# FA18_AMPCD.net
KiCad netlist of a schematic drawn in Altium Designer
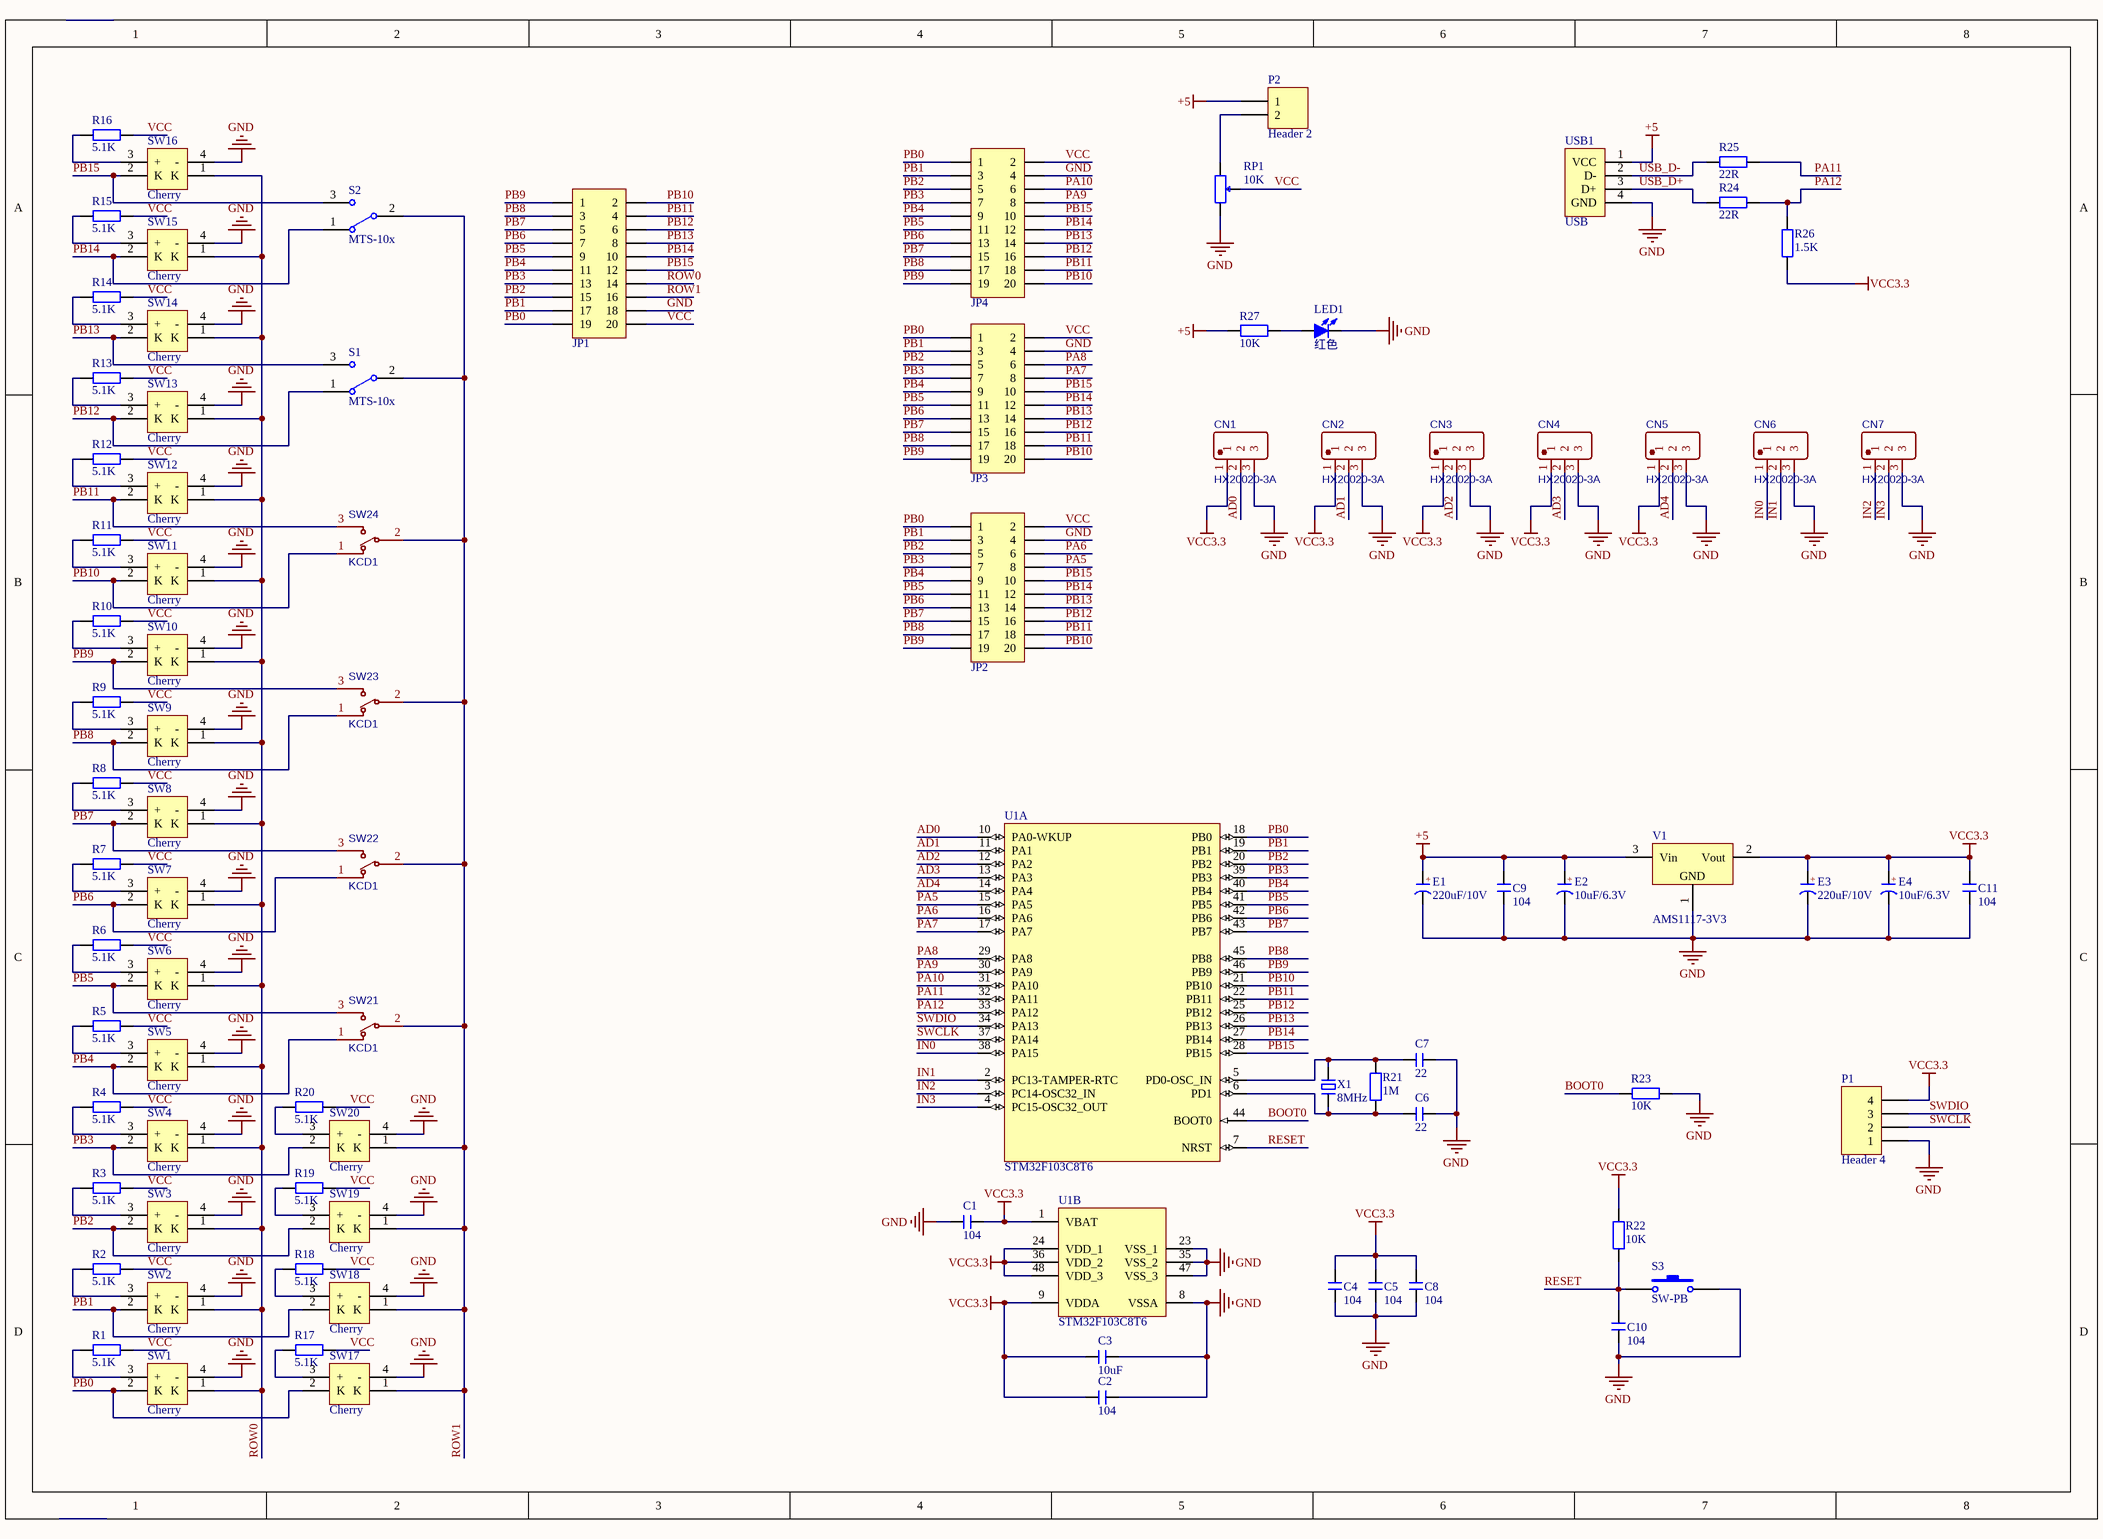
[diagram p0: FA18_AMPCD.SchDoc]

(export (version "E")
  (design (tool "Eeschema 10.0.6"))
  (components
    (comp (ref "C1")
      (value "104")
      (footprint "C 0603_L")
      (description "贴片电容")
      (libsource (lib "wyc_lib") (part "C"))
    )
    (comp (ref "C2")
      (value "104")
      (footprint "C 0603_L")
      (description "贴片电容")
      (libsource (lib "wyc_lib") (part "C"))
    )
    (comp (ref "C3")
      (value "10uF")
      (footprint "C 0603_L")
      (description "贴片电容")
      (libsource (lib "wyc_lib") (part "C"))
    )
    (comp (ref "C4")
      (value "104")
      (footprint "C 0603_L")
      (description "贴片电容")
      (libsource (lib "wyc_lib") (part "C"))
    )
    (comp (ref "C5")
      (value "104")
      (footprint "C 0603_L")
      (description "贴片电容")
      (libsource (lib "wyc_lib") (part "C"))
    )
    (comp (ref "C6")
      (value "22")
      (footprint "C 0603_L")
      (description "贴片电容")
      (libsource (lib "wyc_lib") (part "C"))
    )
    (comp (ref "C7")
      (value "22")
      (footprint "C 0603_L")
      (description "贴片电容")
      (libsource (lib "wyc_lib") (part "C"))
    )
    (comp (ref "C8")
      (value "104")
      (footprint "C 0603_L")
      (description "贴片电容")
      (libsource (lib "wyc_lib") (part "C"))
    )
    (comp (ref "C9")
      (value "104")
      (footprint "C 0603_L")
      (description "贴片电容")
      (libsource (lib "wyc_lib") (part "C"))
    )
    (comp (ref "C10")
      (value "104")
      (footprint "C 0603_L")
      (description "贴片电容")
      (libsource (lib "wyc_lib") (part "C"))
    )
    (comp (ref "C11")
      (value "104")
      (footprint "C 0603_L")
      (description "贴片电容")
      (libsource (lib "wyc_lib") (part "C"))
    )
    (comp (ref "CN1")
      (value "HX20020-3A")
      (footprint "CONN-TH_3P-P2.00_HX20020-3A")
      (fields (field (name "BOM_SUPPLIER PART") "C442245") (field (name "CONTRIBUTOR") "LCSC"))
      (libsource (lib "lichuang_lib") (part "HX20020-3A"))
    )
    (comp (ref "CN2")
      (value "HX20020-3A")
      (footprint "CONN-TH_3P-P2.00_HX20020-3A")
      (fields (field (name "BOM_SUPPLIER PART") "C442245") (field (name "CONTRIBUTOR") "LCSC"))
      (libsource (lib "lichuang_lib") (part "HX20020-3A"))
    )
    (comp (ref "CN3")
      (value "HX20020-3A")
      (footprint "CONN-TH_3P-P2.00_HX20020-3A")
      (fields (field (name "BOM_SUPPLIER PART") "C442245") (field (name "CONTRIBUTOR") "LCSC"))
      (libsource (lib "lichuang_lib") (part "HX20020-3A"))
    )
    (comp (ref "CN4")
      (value "HX20020-3A")
      (footprint "CONN-TH_3P-P2.00_HX20020-3A")
      (fields (field (name "BOM_SUPPLIER PART") "C442245") (field (name "CONTRIBUTOR") "LCSC"))
      (libsource (lib "lichuang_lib") (part "HX20020-3A"))
    )
    (comp (ref "CN5")
      (value "HX20020-3A")
      (footprint "CONN-TH_3P-P2.00_HX20020-3A")
      (fields (field (name "BOM_SUPPLIER PART") "C442245") (field (name "CONTRIBUTOR") "LCSC"))
      (libsource (lib "lichuang_lib") (part "HX20020-3A"))
    )
    (comp (ref "CN6")
      (value "HX20020-3A")
      (footprint "CONN-TH_3P-P2.00_HX20020-3A")
      (fields (field (name "BOM_SUPPLIER PART") "C442245") (field (name "CONTRIBUTOR") "LCSC"))
      (libsource (lib "lichuang_lib") (part "HX20020-3A"))
    )
    (comp (ref "CN7")
      (value "HX20020-3A")
      (footprint "CONN-TH_3P-P2.00_HX20020-3A")
      (fields (field (name "BOM_SUPPLIER PART") "C442245") (field (name "CONTRIBUTOR") "LCSC"))
      (libsource (lib "lichuang_lib") (part "HX20020-3A"))
    )
    (comp (ref "E1")
      (value "220uF/10V")
      (footprint "CM D(6.3*5.4)")
      (description "贴片电解电容")
      (fields (field (name "版权归属") "封装库来自淘宝 ID：黄晶宝石"))
      (libsource (lib "wyc_lib") (part "CE_SMD"))
    )
    (comp (ref "E2")
      (value "10uF/6.3V")
      (footprint "CD B(3528)")
      (description "贴片钽电容")
      (libsource (lib "wyc_lib") (part "CT"))
    )
    (comp (ref "E3")
      (value "220uF/10V")
      (footprint "CM D(6.3*5.4)")
      (description "贴片电解电容")
      (fields (field (name "版权归属") "封装库来自淘宝 ID：黄晶宝石"))
      (libsource (lib "wyc_lib") (part "CE_SMD"))
    )
    (comp (ref "E4")
      (value "10uF/6.3V")
      (footprint "CD B(3528)")
      (description "贴片钽电容")
      (libsource (lib "wyc_lib") (part "CT"))
    )
    (comp (ref "JP1")
      (value "Header 2X10")
      (footprint "PHB2.0-LI-2x10P")
      (description "10*2P接插件")
      (libsource (lib "wyc_lib") (part "Header 10X2"))
    )
    (comp (ref "JP2")
      (value "Header 2X10")
      (footprint "PHB2.0-LI-2x10P")
      (description "10*2P接插件")
      (libsource (lib "wyc_lib") (part "Header 10X2"))
    )
    (comp (ref "JP3")
      (value "Header 2X10")
      (footprint "PHB2.0-LI-2x10P")
      (description "10*2P接插件")
      (libsource (lib "wyc_lib") (part "Header 10X2"))
    )
    (comp (ref "JP4")
      (value "Header 2X10")
      (footprint "PHB2.0-LI-2x10P")
      (description "10*2P接插件")
      (libsource (lib "wyc_lib") (part "Header 10X2"))
    )
    (comp (ref "LED1")
      (value "红色")
      (footprint "LED 0603W")
      (description "贴片LED")
      (fields (field (name "版权归属") "封装库来自淘宝 ID：黄晶宝石"))
      (libsource (lib "wyc_lib") (part "LED-SMD"))
    )
    (comp (ref "P1")
      (value "Header 4")
      (footprint "HDR1X4")
      (description "Header, 4-Pin")
      (fields (field (name "PUBLISHER") "Altium Limited"))
      (libsource (lib "Miscellaneous Connectors") (part "Header 4"))
    )
    (comp (ref "P2")
      (value "Header 2")
      (footprint "HDR1X2")
      (description "Header, 2-Pin")
      (fields (field (name "PUBLISHER") "Altium Limited"))
      (libsource (lib "Miscellaneous Connectors") (part "Header 2"))
    )
    (comp (ref "R1")
      (value "5.1K")
      (footprint "R 0603_L")
      (description "贴片电阻")
      (fields (field (name "版权归属") "来自淘宝 ID：黄晶宝石"))
      (libsource (lib "wyc_lib") (part "R"))
    )
    (comp (ref "R2")
      (value "5.1K")
      (footprint "R 0603_L")
      (description "贴片电阻")
      (fields (field (name "版权归属") "来自淘宝 ID：黄晶宝石"))
      (libsource (lib "wyc_lib") (part "R"))
    )
    (comp (ref "R3")
      (value "5.1K")
      (footprint "R 0603_L")
      (description "贴片电阻")
      (fields (field (name "版权归属") "来自淘宝 ID：黄晶宝石"))
      (libsource (lib "wyc_lib") (part "R"))
    )
    (comp (ref "R4")
      (value "5.1K")
      (footprint "R 0603_L")
      (description "贴片电阻")
      (fields (field (name "版权归属") "来自淘宝 ID：黄晶宝石"))
      (libsource (lib "wyc_lib") (part "R"))
    )
    (comp (ref "R5")
      (value "5.1K")
      (footprint "R 0603_L")
      (description "贴片电阻")
      (fields (field (name "版权归属") "来自淘宝 ID：黄晶宝石"))
      (libsource (lib "wyc_lib") (part "R"))
    )
    (comp (ref "R6")
      (value "5.1K")
      (footprint "R 0603_L")
      (description "贴片电阻")
      (fields (field (name "版权归属") "来自淘宝 ID：黄晶宝石"))
      (libsource (lib "wyc_lib") (part "R"))
    )
    (comp (ref "R7")
      (value "5.1K")
      (footprint "R 0603_L")
      (description "贴片电阻")
      (fields (field (name "版权归属") "来自淘宝 ID：黄晶宝石"))
      (libsource (lib "wyc_lib") (part "R"))
    )
    (comp (ref "R8")
      (value "5.1K")
      (footprint "R 0603_L")
      (description "贴片电阻")
      (fields (field (name "版权归属") "来自淘宝 ID：黄晶宝石"))
      (libsource (lib "wyc_lib") (part "R"))
    )
    (comp (ref "R9")
      (value "5.1K")
      (footprint "R 0603_L")
      (description "贴片电阻")
      (fields (field (name "版权归属") "来自淘宝 ID：黄晶宝石"))
      (libsource (lib "wyc_lib") (part "R"))
    )
    (comp (ref "R10")
      (value "5.1K")
      (footprint "R 0603_L")
      (description "贴片电阻")
      (fields (field (name "版权归属") "来自淘宝 ID：黄晶宝石"))
      (libsource (lib "wyc_lib") (part "R"))
    )
    (comp (ref "R11")
      (value "5.1K")
      (footprint "R 0603_L")
      (description "贴片电阻")
      (fields (field (name "版权归属") "来自淘宝 ID：黄晶宝石"))
      (libsource (lib "wyc_lib") (part "R"))
    )
    (comp (ref "R12")
      (value "5.1K")
      (footprint "R 0603_L")
      (description "贴片电阻")
      (fields (field (name "版权归属") "来自淘宝 ID：黄晶宝石"))
      (libsource (lib "wyc_lib") (part "R"))
    )
    (comp (ref "R13")
      (value "5.1K")
      (footprint "R 0603_L")
      (description "贴片电阻")
      (fields (field (name "版权归属") "来自淘宝 ID：黄晶宝石"))
      (libsource (lib "wyc_lib") (part "R"))
    )
    (comp (ref "R14")
      (value "5.1K")
      (footprint "R 0603_L")
      (description "贴片电阻")
      (fields (field (name "版权归属") "来自淘宝 ID：黄晶宝石"))
      (libsource (lib "wyc_lib") (part "R"))
    )
    (comp (ref "R15")
      (value "5.1K")
      (footprint "R 0603_L")
      (description "贴片电阻")
      (fields (field (name "版权归属") "来自淘宝 ID：黄晶宝石"))
      (libsource (lib "wyc_lib") (part "R"))
    )
    (comp (ref "R16")
      (value "5.1K")
      (footprint "R 0603_L")
      (description "贴片电阻")
      (fields (field (name "版权归属") "来自淘宝 ID：黄晶宝石"))
      (libsource (lib "wyc_lib") (part "R"))
    )
    (comp (ref "R17")
      (value "5.1K")
      (footprint "R 0603_L")
      (description "贴片电阻")
      (fields (field (name "版权归属") "来自淘宝 ID：黄晶宝石"))
      (libsource (lib "wyc_lib") (part "R"))
    )
    (comp (ref "R18")
      (value "5.1K")
      (footprint "R 0603_L")
      (description "贴片电阻")
      (fields (field (name "版权归属") "来自淘宝 ID：黄晶宝石"))
      (libsource (lib "wyc_lib") (part "R"))
    )
    (comp (ref "R19")
      (value "5.1K")
      (footprint "R 0603_L")
      (description "贴片电阻")
      (fields (field (name "版权归属") "来自淘宝 ID：黄晶宝石"))
      (libsource (lib "wyc_lib") (part "R"))
    )
    (comp (ref "R20")
      (value "5.1K")
      (footprint "R 0603_L")
      (description "贴片电阻")
      (fields (field (name "版权归属") "来自淘宝 ID：黄晶宝石"))
      (libsource (lib "wyc_lib") (part "R"))
    )
    (comp (ref "R21")
      (value "1M")
      (footprint "R 0603_L")
      (description "贴片电阻")
      (fields (field (name "版权归属") "来自淘宝 ID：黄晶宝石"))
      (libsource (lib "wyc_lib") (part "R"))
    )
    (comp (ref "R22")
      (value "10K")
      (footprint "R 0603_L")
      (description "贴片电阻")
      (fields (field (name "版权归属") "来自淘宝 ID：黄晶宝石"))
      (libsource (lib "wyc_lib") (part "R"))
    )
    (comp (ref "R23")
      (value "10K")
      (footprint "R 0603_L")
      (description "贴片电阻")
      (fields (field (name "版权归属") "来自淘宝 ID：黄晶宝石"))
      (libsource (lib "wyc_lib") (part "R"))
    )
    (comp (ref "R24")
      (value "22R")
      (footprint "R 0603_L")
      (description "贴片电阻")
      (fields (field (name "版权归属") "来自淘宝 ID：黄晶宝石"))
      (libsource (lib "wyc_lib") (part "R"))
    )
    (comp (ref "R25")
      (value "22R")
      (footprint "R 0603_L")
      (description "贴片电阻")
      (fields (field (name "版权归属") "来自淘宝 ID：黄晶宝石"))
      (libsource (lib "wyc_lib") (part "R"))
    )
    (comp (ref "R26")
      (value "1.5K")
      (footprint "R 0603_L")
      (description "贴片电阻")
      (fields (field (name "版权归属") "来自淘宝 ID：黄晶宝石"))
      (libsource (lib "wyc_lib") (part "R"))
    )
    (comp (ref "R27")
      (value "10K")
      (footprint "R 0603_L")
      (description "贴片电阻")
      (fields (field (name "版权归属") "来自淘宝 ID：黄晶宝石"))
      (libsource (lib "wyc_lib") (part "R"))
    )
    (comp (ref "RP1")
      (value "10K")
      (footprint "WH148-1-G15")
      (description "单联电位器")
      (fields (field (name "版权归属") "封装库来自淘宝 ID：黄晶宝石"))
      (libsource (lib "wyc_lib") (part "RP"))
    )
    (comp (ref "S1")
      (value "MTS-10x")
      (footprint "MTS-10x")
      (description "MTS10x系列3脚扭子开关")
      (fields (field (name "版权归属") "封装库来自淘宝 ID：黄晶宝石"))
      (libsource (lib "wyc_lib") (part "MTS-10x"))
    )
    (comp (ref "S2")
      (value "MTS-10x")
      (footprint "MTS-10x")
      (description "MTS10x系列3脚扭子开关")
      (fields (field (name "版权归属") "封装库来自淘宝 ID：黄晶宝石"))
      (libsource (lib "wyc_lib") (part "MTS-10x"))
    )
    (comp (ref "S3")
      (value "SW-PB")
      (footprint "SW_PB2_A1")
      (description "微动开关")
      (fields (field (name "PUBLISHER") "Altium Limited"))
      (libsource (lib "wyc_lib") (part "SW-PB"))
    )
    (comp (ref "SW1")
      (value "Cherry")
      (footprint "LSW DIP-CHERRY")
      (description "带灯机械按键开关")
      (fields (field (name "版权归属") "封装库来自淘宝 ID：黄晶宝石"))
      (libsource (lib "wyc_lib") (part "LSW"))
    )
    (comp (ref "SW2")
      (value "Cherry")
      (footprint "LSW DIP-CHERRY")
      (description "带灯机械按键开关")
      (fields (field (name "版权归属") "封装库来自淘宝 ID：黄晶宝石"))
      (libsource (lib "wyc_lib") (part "LSW"))
    )
    (comp (ref "SW3")
      (value "Cherry")
      (footprint "LSW DIP-CHERRY")
      (description "带灯机械按键开关")
      (fields (field (name "版权归属") "封装库来自淘宝 ID：黄晶宝石"))
      (libsource (lib "wyc_lib") (part "LSW"))
    )
    (comp (ref "SW4")
      (value "Cherry")
      (footprint "LSW DIP-CHERRY")
      (description "带灯机械按键开关")
      (fields (field (name "版权归属") "封装库来自淘宝 ID：黄晶宝石"))
      (libsource (lib "wyc_lib") (part "LSW"))
    )
    (comp (ref "SW5")
      (value "Cherry")
      (footprint "LSW DIP-CHERRY")
      (description "带灯机械按键开关")
      (fields (field (name "版权归属") "封装库来自淘宝 ID：黄晶宝石"))
      (libsource (lib "wyc_lib") (part "LSW"))
    )
    (comp (ref "SW6")
      (value "Cherry")
      (footprint "LSW DIP-CHERRY")
      (description "带灯机械按键开关")
      (fields (field (name "版权归属") "封装库来自淘宝 ID：黄晶宝石"))
      (libsource (lib "wyc_lib") (part "LSW"))
    )
    (comp (ref "SW7")
      (value "Cherry")
      (footprint "LSW DIP-CHERRY")
      (description "带灯机械按键开关")
      (fields (field (name "版权归属") "封装库来自淘宝 ID：黄晶宝石"))
      (libsource (lib "wyc_lib") (part "LSW"))
    )
    (comp (ref "SW8")
      (value "Cherry")
      (footprint "LSW DIP-CHERRY")
      (description "带灯机械按键开关")
      (fields (field (name "版权归属") "封装库来自淘宝 ID：黄晶宝石"))
      (libsource (lib "wyc_lib") (part "LSW"))
    )
    (comp (ref "SW9")
      (value "Cherry")
      (footprint "LSW DIP-CHERRY")
      (description "带灯机械按键开关")
      (fields (field (name "版权归属") "封装库来自淘宝 ID：黄晶宝石"))
      (libsource (lib "wyc_lib") (part "LSW"))
    )
    (comp (ref "SW10")
      (value "Cherry")
      (footprint "LSW DIP-CHERRY")
      (description "带灯机械按键开关")
      (fields (field (name "版权归属") "封装库来自淘宝 ID：黄晶宝石"))
      (libsource (lib "wyc_lib") (part "LSW"))
    )
    (comp (ref "SW11")
      (value "Cherry")
      (footprint "LSW DIP-CHERRY")
      (description "带灯机械按键开关")
      (fields (field (name "版权归属") "封装库来自淘宝 ID：黄晶宝石"))
      (libsource (lib "wyc_lib") (part "LSW"))
    )
    (comp (ref "SW12")
      (value "Cherry")
      (footprint "LSW DIP-CHERRY")
      (description "带灯机械按键开关")
      (fields (field (name "版权归属") "封装库来自淘宝 ID：黄晶宝石"))
      (libsource (lib "wyc_lib") (part "LSW"))
    )
    (comp (ref "SW13")
      (value "Cherry")
      (footprint "LSW DIP-CHERRY")
      (description "带灯机械按键开关")
      (fields (field (name "版权归属") "封装库来自淘宝 ID：黄晶宝石"))
      (libsource (lib "wyc_lib") (part "LSW"))
    )
    (comp (ref "SW14")
      (value "Cherry")
      (footprint "LSW DIP-CHERRY")
      (description "带灯机械按键开关")
      (fields (field (name "版权归属") "封装库来自淘宝 ID：黄晶宝石"))
      (libsource (lib "wyc_lib") (part "LSW"))
    )
    (comp (ref "SW15")
      (value "Cherry")
      (footprint "LSW DIP-CHERRY")
      (description "带灯机械按键开关")
      (fields (field (name "版权归属") "封装库来自淘宝 ID：黄晶宝石"))
      (libsource (lib "wyc_lib") (part "LSW"))
    )
    (comp (ref "SW16")
      (value "Cherry")
      (footprint "LSW DIP-CHERRY")
      (description "带灯机械按键开关")
      (fields (field (name "版权归属") "封装库来自淘宝 ID：黄晶宝石"))
      (libsource (lib "wyc_lib") (part "LSW"))
    )
    (comp (ref "SW17")
      (value "Cherry")
      (footprint "LSW DIP-CHERRY")
      (description "带灯机械按键开关")
      (fields (field (name "版权归属") "封装库来自淘宝 ID：黄晶宝石"))
      (libsource (lib "wyc_lib") (part "LSW"))
    )
    (comp (ref "SW18")
      (value "Cherry")
      (footprint "LSW DIP-CHERRY")
      (description "带灯机械按键开关")
      (fields (field (name "版权归属") "封装库来自淘宝 ID：黄晶宝石"))
      (libsource (lib "wyc_lib") (part "LSW"))
    )
    (comp (ref "SW19")
      (value "Cherry")
      (footprint "LSW DIP-CHERRY")
      (description "带灯机械按键开关")
      (fields (field (name "版权归属") "封装库来自淘宝 ID：黄晶宝石"))
      (libsource (lib "wyc_lib") (part "LSW"))
    )
    (comp (ref "SW20")
      (value "Cherry")
      (footprint "LSW DIP-CHERRY")
      (description "带灯机械按键开关")
      (fields (field (name "版权归属") "封装库来自淘宝 ID：黄晶宝石"))
      (libsource (lib "wyc_lib") (part "LSW"))
    )
    (comp (ref "SW21")
      (value "KCD1")
      (footprint "KCD1")
      (description "船型开关")
      (fields
        (field (name "BOM_SUPPLIER PART") "C268223")
        (field (name "BOM_MANUFACTURER PART") "MR1-138-C6N-BBAA")
        (field (name "CONTRIBUTOR") "LCSC")
      )
      (libsource (lib "lichuang_lib") (part "KCD1"))
    )
    (comp (ref "SW22")
      (value "KCD1")
      (footprint "KCD1")
      (description "船型开关")
      (fields
        (field (name "BOM_SUPPLIER PART") "C268223")
        (field (name "BOM_MANUFACTURER PART") "MR1-138-C6N-BBAA")
        (field (name "CONTRIBUTOR") "LCSC")
      )
      (libsource (lib "lichuang_lib") (part "KCD1"))
    )
    (comp (ref "SW23")
      (value "KCD1")
      (footprint "KCD1")
      (description "船型开关")
      (fields
        (field (name "BOM_SUPPLIER PART") "C268223")
        (field (name "BOM_MANUFACTURER PART") "MR1-138-C6N-BBAA")
        (field (name "CONTRIBUTOR") "LCSC")
      )
      (libsource (lib "lichuang_lib") (part "KCD1"))
    )
    (comp (ref "SW24")
      (value "KCD1")
      (footprint "KCD1")
      (description "船型开关")
      (fields
        (field (name "BOM_SUPPLIER PART") "C268223")
        (field (name "BOM_MANUFACTURER PART") "MR1-138-C6N-BBAA")
        (field (name "CONTRIBUTOR") "LCSC")
      )
      (libsource (lib "lichuang_lib") (part "KCD1"))
    )
    (comp (ref "U1")
      (value "STM32F103C8T6")
      (footprint "LQFP48_N")
      (libsource (lib "wyc_lib") (part "STM32F103C8T6"))
    )
    (comp (ref "USB1")
      (value "USB")
      (footprint "USB-B/S_A")
      (description "USB-B型母接口")
      (fields (field (name "版权归属") "封装库来自淘宝 ID：黄晶宝石"))
      (libsource (lib "wyc_lib") (part "USB-B/S"))
    )
    (comp (ref "V1")
      (value "AMS1117-3V3")
      (footprint "SOT223_L")
      (description "三端稳压芯片")
      (libsource (lib "wyc_lib") (part "AMS1117"))
    )
    (comp (ref "X1")
      (value "8MHz")
      (footprint "OSC HC-49S")
      (description "2脚无源脚晶振")
      (fields (field (name "版权归属") "封装库来自淘宝卖家 ID：黄晶宝石"))
      (libsource (lib "wyc_lib") (part "XTAL-2P"))
    )
  )
  (nets
    (net (code "1") (name "+5") (class "Default")
      (node (ref "C9") (pin "2") (pinfunction "2_2") (pintype "passive"))
      (node (ref "E1") (pin "1") (pinfunction "A_1") (pintype "passive"))
      (node (ref "E2") (pin "1") (pinfunction "A_1") (pintype "passive"))
      (node (ref "P2") (pin "1") (pinfunction "1_1") (pintype "passive"))
      (node (ref "R27") (pin "1") (pinfunction "1_1") (pintype "passive"))
      (node (ref "USB1") (pin "1") (pinfunction "VCC_1") (pintype "passive"))
      (node (ref "V1") (pin "3") (pinfunction "Vin_3") (pintype "passive"))
    )
    (net (code "2") (name "/AD0") (class "Default")
      (node (ref "CN1") (pin "2") (pinfunction "2_2") (pintype "passive"))
      (node (ref "U1") (pin "10") (pinfunction "PA0-WKUP_10") (pintype "bidirectional"))
    )
    (net (code "3") (name "/AD1") (class "Default")
      (node (ref "CN2") (pin "2") (pinfunction "2_2") (pintype "passive"))
      (node (ref "U1") (pin "11") (pinfunction "PA1_11") (pintype "bidirectional"))
    )
    (net (code "4") (name "/AD2") (class "Default")
      (node (ref "CN3") (pin "2") (pinfunction "2_2") (pintype "passive"))
      (node (ref "U1") (pin "12") (pinfunction "PA2_12") (pintype "bidirectional"))
    )
    (net (code "5") (name "/AD3") (class "Default")
      (node (ref "CN4") (pin "2") (pinfunction "2_2") (pintype "passive"))
      (node (ref "U1") (pin "13") (pinfunction "PA3_13") (pintype "bidirectional"))
    )
    (net (code "6") (name "/AD4") (class "Default")
      (node (ref "CN5") (pin "2") (pinfunction "2_2") (pintype "passive"))
      (node (ref "U1") (pin "14") (pinfunction "PA4_14") (pintype "bidirectional"))
    )
    (net (code "7") (name "/BOOT0") (class "Default")
      (node (ref "R23") (pin "1") (pinfunction "1_1") (pintype "passive"))
      (node (ref "U1") (pin "44") (pinfunction "BOOT0_44") (pintype "input"))
    )
    (net (code "8") (name "/IN0") (class "Default")
      (node (ref "CN6") (pin "1") (pinfunction "1_1") (pintype "passive"))
      (node (ref "U1") (pin "38") (pinfunction "PA15_38") (pintype "bidirectional"))
    )
    (net (code "9") (name "/IN1") (class "Default")
      (node (ref "CN6") (pin "2") (pinfunction "2_2") (pintype "passive"))
      (node (ref "U1") (pin "2") (pinfunction "PC13-TAMPER-RTC_2") (pintype "bidirectional"))
    )
    (net (code "10") (name "/IN2") (class "Default")
      (node (ref "CN7") (pin "1") (pinfunction "1_1") (pintype "passive"))
      (node (ref "U1") (pin "3") (pinfunction "PC14-OSC32_IN_3") (pintype "bidirectional"))
    )
    (net (code "11") (name "/IN3") (class "Default")
      (node (ref "CN7") (pin "2") (pinfunction "2_2") (pintype "passive"))
      (node (ref "U1") (pin "4") (pinfunction "PC15-OSC32_OUT_4") (pintype "bidirectional"))
    )
    (net (code "12") (name "/PA5") (class "Default")
      (node (ref "JP2") (pin "8") (pinfunction "8_8") (pintype "passive"))
      (node (ref "U1") (pin "15") (pinfunction "PA5_15") (pintype "bidirectional"))
    )
    (net (code "13") (name "/PA6") (class "Default")
      (node (ref "JP2") (pin "6") (pinfunction "6_6") (pintype "passive"))
      (node (ref "U1") (pin "16") (pinfunction "PA6_16") (pintype "bidirectional"))
    )
    (net (code "14") (name "/PA7") (class "Default")
      (node (ref "JP3") (pin "8") (pinfunction "8_8") (pintype "passive"))
      (node (ref "U1") (pin "17") (pinfunction "PA7_17") (pintype "bidirectional"))
    )
    (net (code "15") (name "/PA8") (class "Default")
      (node (ref "JP3") (pin "6") (pinfunction "6_6") (pintype "passive"))
      (node (ref "U1") (pin "29") (pinfunction "PA8_29") (pintype "bidirectional"))
    )
    (net (code "16") (name "/PA9") (class "Default")
      (node (ref "JP4") (pin "8") (pinfunction "8_8") (pintype "passive"))
      (node (ref "U1") (pin "30") (pinfunction "PA9_30") (pintype "bidirectional"))
    )
    (net (code "17") (name "/PA10") (class "Default")
      (node (ref "JP4") (pin "6") (pinfunction "6_6") (pintype "passive"))
      (node (ref "U1") (pin "31") (pinfunction "PA10_31") (pintype "bidirectional"))
    )
    (net (code "18") (name "/PA11") (class "Default")
      (node (ref "R25") (pin "2") (pinfunction "2_2") (pintype "passive"))
      (node (ref "U1") (pin "32") (pinfunction "PA11_32") (pintype "bidirectional"))
    )
    (net (code "19") (name "/PA12") (class "Default")
      (node (ref "R24") (pin "2") (pinfunction "2_2") (pintype "passive"))
      (node (ref "R26") (pin "2") (pinfunction "2_2") (pintype "passive"))
      (node (ref "U1") (pin "33") (pinfunction "PA12_33") (pintype "bidirectional"))
    )
    (net (code "20") (name "/PB0") (class "Default")
      (node (ref "JP1") (pin "19") (pinfunction "19_19") (pintype "passive"))
      (node (ref "JP2") (pin "1") (pinfunction "1_1") (pintype "passive"))
      (node (ref "JP3") (pin "1") (pinfunction "1_1") (pintype "passive"))
      (node (ref "JP4") (pin "1") (pinfunction "1_1") (pintype "passive"))
      (node (ref "SW1") (pin "2") (pinfunction "K_2") (pintype "passive"))
      (node (ref "SW17") (pin "2") (pinfunction "K_2") (pintype "passive"))
      (node (ref "U1") (pin "18") (pinfunction "PB0_18") (pintype "bidirectional"))
    )
    (net (code "21") (name "/PB1") (class "Default")
      (node (ref "JP1") (pin "17") (pinfunction "17_17") (pintype "passive"))
      (node (ref "JP2") (pin "3") (pinfunction "3_3") (pintype "passive"))
      (node (ref "JP3") (pin "3") (pinfunction "3_3") (pintype "passive"))
      (node (ref "JP4") (pin "3") (pinfunction "3_3") (pintype "passive"))
      (node (ref "SW18") (pin "2") (pinfunction "K_2") (pintype "passive"))
      (node (ref "SW2") (pin "2") (pinfunction "K_2") (pintype "passive"))
      (node (ref "U1") (pin "19") (pinfunction "PB1_19") (pintype "bidirectional"))
    )
    (net (code "22") (name "/PB2") (class "Default")
      (node (ref "JP1") (pin "15") (pinfunction "15_15") (pintype "passive"))
      (node (ref "JP2") (pin "5") (pinfunction "5_5") (pintype "passive"))
      (node (ref "JP3") (pin "5") (pinfunction "5_5") (pintype "passive"))
      (node (ref "JP4") (pin "5") (pinfunction "5_5") (pintype "passive"))
      (node (ref "SW19") (pin "2") (pinfunction "K_2") (pintype "passive"))
      (node (ref "SW3") (pin "2") (pinfunction "K_2") (pintype "passive"))
      (node (ref "U1") (pin "20") (pinfunction "PB2_20") (pintype "bidirectional"))
    )
    (net (code "23") (name "/PB3") (class "Default")
      (node (ref "JP1") (pin "13") (pinfunction "13_13") (pintype "passive"))
      (node (ref "JP2") (pin "7") (pinfunction "7_7") (pintype "passive"))
      (node (ref "JP3") (pin "7") (pinfunction "7_7") (pintype "passive"))
      (node (ref "JP4") (pin "7") (pinfunction "7_7") (pintype "passive"))
      (node (ref "SW20") (pin "2") (pinfunction "K_2") (pintype "passive"))
      (node (ref "SW4") (pin "2") (pinfunction "K_2") (pintype "passive"))
      (node (ref "U1") (pin "39") (pinfunction "PB3_39") (pintype "bidirectional"))
    )
    (net (code "24") (name "/PB4") (class "Default")
      (node (ref "JP1") (pin "11") (pinfunction "11_11") (pintype "passive"))
      (node (ref "JP2") (pin "9") (pinfunction "9_9") (pintype "passive"))
      (node (ref "JP3") (pin "9") (pinfunction "9_9") (pintype "passive"))
      (node (ref "JP4") (pin "9") (pinfunction "9_9") (pintype "passive"))
      (node (ref "SW21") (pin "1") (pinfunction "1_1") (pintype "passive"))
      (node (ref "SW5") (pin "2") (pinfunction "K_2") (pintype "passive"))
      (node (ref "U1") (pin "40") (pinfunction "PB4_40") (pintype "bidirectional"))
    )
    (net (code "25") (name "/PB5") (class "Default")
      (node (ref "JP1") (pin "9") (pinfunction "9_9") (pintype "passive"))
      (node (ref "JP2") (pin "11") (pinfunction "11_11") (pintype "passive"))
      (node (ref "JP3") (pin "11") (pinfunction "11_11") (pintype "passive"))
      (node (ref "JP4") (pin "11") (pinfunction "11_11") (pintype "passive"))
      (node (ref "SW21") (pin "3") (pinfunction "3_3") (pintype "passive"))
      (node (ref "SW6") (pin "2") (pinfunction "K_2") (pintype "passive"))
      (node (ref "U1") (pin "41") (pinfunction "PB5_41") (pintype "bidirectional"))
    )
    (net (code "26") (name "/PB6") (class "Default")
      (node (ref "JP1") (pin "7") (pinfunction "7_7") (pintype "passive"))
      (node (ref "JP2") (pin "13") (pinfunction "13_13") (pintype "passive"))
      (node (ref "JP3") (pin "13") (pinfunction "13_13") (pintype "passive"))
      (node (ref "JP4") (pin "13") (pinfunction "13_13") (pintype "passive"))
      (node (ref "SW22") (pin "1") (pinfunction "1_1") (pintype "passive"))
      (node (ref "SW7") (pin "2") (pinfunction "K_2") (pintype "passive"))
      (node (ref "U1") (pin "42") (pinfunction "PB6_42") (pintype "bidirectional"))
    )
    (net (code "27") (name "/PB7") (class "Default")
      (node (ref "JP1") (pin "5") (pinfunction "5_5") (pintype "passive"))
      (node (ref "JP2") (pin "15") (pinfunction "15_15") (pintype "passive"))
      (node (ref "JP3") (pin "15") (pinfunction "15_15") (pintype "passive"))
      (node (ref "JP4") (pin "15") (pinfunction "15_15") (pintype "passive"))
      (node (ref "SW22") (pin "3") (pinfunction "3_3") (pintype "passive"))
      (node (ref "SW8") (pin "2") (pinfunction "K_2") (pintype "passive"))
      (node (ref "U1") (pin "43") (pinfunction "PB7_43") (pintype "bidirectional"))
    )
    (net (code "28") (name "/PB8") (class "Default")
      (node (ref "JP1") (pin "3") (pinfunction "3_3") (pintype "passive"))
      (node (ref "JP2") (pin "17") (pinfunction "17_17") (pintype "passive"))
      (node (ref "JP3") (pin "17") (pinfunction "17_17") (pintype "passive"))
      (node (ref "JP4") (pin "17") (pinfunction "17_17") (pintype "passive"))
      (node (ref "SW23") (pin "1") (pinfunction "1_1") (pintype "passive"))
      (node (ref "SW9") (pin "2") (pinfunction "K_2") (pintype "passive"))
      (node (ref "U1") (pin "45") (pinfunction "PB8_45") (pintype "bidirectional"))
    )
    (net (code "29") (name "/PB9") (class "Default")
      (node (ref "JP1") (pin "1") (pinfunction "1_1") (pintype "passive"))
      (node (ref "JP2") (pin "19") (pinfunction "19_19") (pintype "passive"))
      (node (ref "JP3") (pin "19") (pinfunction "19_19") (pintype "passive"))
      (node (ref "JP4") (pin "19") (pinfunction "19_19") (pintype "passive"))
      (node (ref "SW10") (pin "2") (pinfunction "K_2") (pintype "passive"))
      (node (ref "SW23") (pin "3") (pinfunction "3_3") (pintype "passive"))
      (node (ref "U1") (pin "46") (pinfunction "PB9_46") (pintype "bidirectional"))
    )
    (net (code "30") (name "/PB10") (class "Default")
      (node (ref "JP1") (pin "2") (pinfunction "2_2") (pintype "passive"))
      (node (ref "JP2") (pin "20") (pinfunction "20_20") (pintype "passive"))
      (node (ref "JP3") (pin "20") (pinfunction "20_20") (pintype "passive"))
      (node (ref "JP4") (pin "20") (pinfunction "20_20") (pintype "passive"))
      (node (ref "SW11") (pin "2") (pinfunction "K_2") (pintype "passive"))
      (node (ref "SW24") (pin "1") (pinfunction "1_1") (pintype "passive"))
      (node (ref "U1") (pin "21") (pinfunction "PB10_21") (pintype "bidirectional"))
    )
    (net (code "31") (name "/PB11") (class "Default")
      (node (ref "JP1") (pin "4") (pinfunction "4_4") (pintype "passive"))
      (node (ref "JP2") (pin "18") (pinfunction "18_18") (pintype "passive"))
      (node (ref "JP3") (pin "18") (pinfunction "18_18") (pintype "passive"))
      (node (ref "JP4") (pin "18") (pinfunction "18_18") (pintype "passive"))
      (node (ref "SW12") (pin "2") (pinfunction "K_2") (pintype "passive"))
      (node (ref "SW24") (pin "3") (pinfunction "3_3") (pintype "passive"))
      (node (ref "U1") (pin "22") (pinfunction "PB11_22") (pintype "bidirectional"))
    )
    (net (code "32") (name "/PB12") (class "Default")
      (node (ref "JP1") (pin "6") (pinfunction "6_6") (pintype "passive"))
      (node (ref "JP2") (pin "16") (pinfunction "16_16") (pintype "passive"))
      (node (ref "JP3") (pin "16") (pinfunction "16_16") (pintype "passive"))
      (node (ref "JP4") (pin "16") (pinfunction "16_16") (pintype "passive"))
      (node (ref "S1") (pin "1") (pinfunction "1_1") (pintype "passive"))
      (node (ref "SW13") (pin "2") (pinfunction "K_2") (pintype "passive"))
      (node (ref "U1") (pin "25") (pinfunction "PB12_25") (pintype "bidirectional"))
    )
    (net (code "33") (name "/PB13") (class "Default")
      (node (ref "JP1") (pin "8") (pinfunction "8_8") (pintype "passive"))
      (node (ref "JP2") (pin "14") (pinfunction "14_14") (pintype "passive"))
      (node (ref "JP3") (pin "14") (pinfunction "14_14") (pintype "passive"))
      (node (ref "JP4") (pin "14") (pinfunction "14_14") (pintype "passive"))
      (node (ref "S1") (pin "3") (pinfunction "3_3") (pintype "passive"))
      (node (ref "SW14") (pin "2") (pinfunction "K_2") (pintype "passive"))
      (node (ref "U1") (pin "26") (pinfunction "PB13_26") (pintype "bidirectional"))
    )
    (net (code "34") (name "/PB14") (class "Default")
      (node (ref "JP1") (pin "10") (pinfunction "10_10") (pintype "passive"))
      (node (ref "JP2") (pin "12") (pinfunction "12_12") (pintype "passive"))
      (node (ref "JP3") (pin "12") (pinfunction "12_12") (pintype "passive"))
      (node (ref "JP4") (pin "12") (pinfunction "12_12") (pintype "passive"))
      (node (ref "S2") (pin "1") (pinfunction "1_1") (pintype "passive"))
      (node (ref "SW15") (pin "2") (pinfunction "K_2") (pintype "passive"))
      (node (ref "U1") (pin "27") (pinfunction "PB14_27") (pintype "bidirectional"))
    )
    (net (code "35") (name "/PB15") (class "Default")
      (node (ref "JP1") (pin "12") (pinfunction "12_12") (pintype "passive"))
      (node (ref "JP2") (pin "10") (pinfunction "10_10") (pintype "passive"))
      (node (ref "JP3") (pin "10") (pinfunction "10_10") (pintype "passive"))
      (node (ref "JP4") (pin "10") (pinfunction "10_10") (pintype "passive"))
      (node (ref "S2") (pin "3") (pinfunction "3_3") (pintype "passive"))
      (node (ref "SW16") (pin "2") (pinfunction "K_2") (pintype "passive"))
      (node (ref "U1") (pin "28") (pinfunction "PB15_28") (pintype "bidirectional"))
    )
    (net (code "36") (name "/RESET") (class "Default")
      (node (ref "C10") (pin "1") (pinfunction "1_1") (pintype "passive"))
      (node (ref "R22") (pin "1") (pinfunction "1_1") (pintype "passive"))
      (node (ref "S3") (pin "1") (pinfunction "1_1") (pintype "passive"))
      (node (ref "U1") (pin "7") (pinfunction "NRST_7") (pintype "bidirectional"))
    )
    (net (code "37") (name "/ROW0") (class "Default")
      (node (ref "JP1") (pin "14") (pinfunction "14_14") (pintype "passive"))
      (node (ref "SW1") (pin "1") (pinfunction "K_1") (pintype "passive"))
      (node (ref "SW10") (pin "1") (pinfunction "K_1") (pintype "passive"))
      (node (ref "SW11") (pin "1") (pinfunction "K_1") (pintype "passive"))
      (node (ref "SW12") (pin "1") (pinfunction "K_1") (pintype "passive"))
      (node (ref "SW13") (pin "1") (pinfunction "K_1") (pintype "passive"))
      (node (ref "SW14") (pin "1") (pinfunction "K_1") (pintype "passive"))
      (node (ref "SW15") (pin "1") (pinfunction "K_1") (pintype "passive"))
      (node (ref "SW16") (pin "1") (pinfunction "K_1") (pintype "passive"))
      (node (ref "SW2") (pin "1") (pinfunction "K_1") (pintype "passive"))
      (node (ref "SW3") (pin "1") (pinfunction "K_1") (pintype "passive"))
      (node (ref "SW4") (pin "1") (pinfunction "K_1") (pintype "passive"))
      (node (ref "SW5") (pin "1") (pinfunction "K_1") (pintype "passive"))
      (node (ref "SW6") (pin "1") (pinfunction "K_1") (pintype "passive"))
      (node (ref "SW7") (pin "1") (pinfunction "K_1") (pintype "passive"))
      (node (ref "SW8") (pin "1") (pinfunction "K_1") (pintype "passive"))
      (node (ref "SW9") (pin "1") (pinfunction "K_1") (pintype "passive"))
    )
    (net (code "38") (name "/ROW1") (class "Default")
      (node (ref "JP1") (pin "16") (pinfunction "16_16") (pintype "passive"))
      (node (ref "S1") (pin "2") (pinfunction "2_2") (pintype "passive"))
      (node (ref "S2") (pin "2") (pinfunction "2_2") (pintype "passive"))
      (node (ref "SW17") (pin "1") (pinfunction "K_1") (pintype "passive"))
      (node (ref "SW18") (pin "1") (pinfunction "K_1") (pintype "passive"))
      (node (ref "SW19") (pin "1") (pinfunction "K_1") (pintype "passive"))
      (node (ref "SW20") (pin "1") (pinfunction "K_1") (pintype "passive"))
      (node (ref "SW21") (pin "2") (pinfunction "2_2") (pintype "passive"))
      (node (ref "SW22") (pin "2") (pinfunction "2_2") (pintype "passive"))
      (node (ref "SW23") (pin "2") (pinfunction "2_2") (pintype "passive"))
      (node (ref "SW24") (pin "2") (pinfunction "2_2") (pintype "passive"))
    )
    (net (code "39") (name "/SWCLK") (class "Default")
      (node (ref "P1") (pin "2") (pinfunction "2_2") (pintype "passive"))
      (node (ref "U1") (pin "37") (pinfunction "PA14_37") (pintype "bidirectional"))
    )
    (net (code "40") (name "/SWDIO") (class "Default")
      (node (ref "P1") (pin "3") (pinfunction "3_3") (pintype "passive"))
      (node (ref "U1") (pin "34") (pinfunction "PA13_34") (pintype "bidirectional"))
    )
    (net (code "41") (name "/USB_D+") (class "Default")
      (node (ref "R24") (pin "1") (pinfunction "1_1") (pintype "passive"))
      (node (ref "USB1") (pin "3") (pinfunction "D+_3") (pintype "passive"))
    )
    (net (code "42") (name "/USB_D-") (class "Default")
      (node (ref "R25") (pin "1") (pinfunction "1_1") (pintype "passive"))
      (node (ref "USB1") (pin "2") (pinfunction "D-_2") (pintype "passive"))
    )
    (net (code "43") (name "/VCC") (class "Default")
      (node (ref "JP1") (pin "20") (pinfunction "20_20") (pintype "passive"))
      (node (ref "JP2") (pin "2") (pinfunction "2_2") (pintype "passive"))
      (node (ref "JP3") (pin "2") (pinfunction "2_2") (pintype "passive"))
      (node (ref "JP4") (pin "2") (pinfunction "2_2") (pintype "passive"))
      (node (ref "R1") (pin "2") (pinfunction "2_2") (pintype "passive"))
      (node (ref "R10") (pin "2") (pinfunction "2_2") (pintype "passive"))
      (node (ref "R11") (pin "2") (pinfunction "2_2") (pintype "passive"))
      (node (ref "R12") (pin "2") (pinfunction "2_2") (pintype "passive"))
      (node (ref "R13") (pin "2") (pinfunction "2_2") (pintype "passive"))
      (node (ref "R14") (pin "2") (pinfunction "2_2") (pintype "passive"))
      (node (ref "R15") (pin "2") (pinfunction "2_2") (pintype "passive"))
      (node (ref "R16") (pin "2") (pinfunction "2_2") (pintype "passive"))
      (node (ref "R17") (pin "2") (pinfunction "2_2") (pintype "passive"))
      (node (ref "R18") (pin "2") (pinfunction "2_2") (pintype "passive"))
      (node (ref "R19") (pin "2") (pinfunction "2_2") (pintype "passive"))
      (node (ref "R2") (pin "2") (pinfunction "2_2") (pintype "passive"))
      (node (ref "R20") (pin "2") (pinfunction "2_2") (pintype "passive"))
      (node (ref "R3") (pin "2") (pinfunction "2_2") (pintype "passive"))
      (node (ref "R4") (pin "2") (pinfunction "2_2") (pintype "passive"))
      (node (ref "R5") (pin "2") (pinfunction "2_2") (pintype "passive"))
      (node (ref "R6") (pin "2") (pinfunction "2_2") (pintype "passive"))
      (node (ref "R7") (pin "2") (pinfunction "2_2") (pintype "passive"))
      (node (ref "R8") (pin "2") (pinfunction "2_2") (pintype "passive"))
      (node (ref "R9") (pin "2") (pinfunction "2_2") (pintype "passive"))
      (node (ref "RP1") (pin "2") (pinfunction "2_2") (pintype "passive"))
    )
    (net (code "44") (name "GND") (class "Default")
      (node (ref "C1") (pin "1") (pinfunction "1_1") (pintype "passive"))
      (node (ref "C10") (pin "2") (pinfunction "2_2") (pintype "passive"))
      (node (ref "C11") (pin "1") (pinfunction "1_1") (pintype "passive"))
      (node (ref "C2") (pin "2") (pinfunction "2_2") (pintype "passive"))
      (node (ref "C3") (pin "2") (pinfunction "2_2") (pintype "passive"))
      (node (ref "C4") (pin "1") (pinfunction "1_1") (pintype "passive"))
      (node (ref "C5") (pin "1") (pinfunction "1_1") (pintype "passive"))
      (node (ref "C6") (pin "2") (pinfunction "2_2") (pintype "passive"))
      (node (ref "C7") (pin "2") (pinfunction "2_2") (pintype "passive"))
      (node (ref "C8") (pin "1") (pinfunction "1_1") (pintype "passive"))
      (node (ref "C9") (pin "1") (pinfunction "1_1") (pintype "passive"))
      (node (ref "CN1") (pin "3") (pinfunction "3_3") (pintype "passive"))
      (node (ref "CN2") (pin "3") (pinfunction "3_3") (pintype "passive"))
      (node (ref "CN3") (pin "3") (pinfunction "3_3") (pintype "passive"))
      (node (ref "CN4") (pin "3") (pinfunction "3_3") (pintype "passive"))
      (node (ref "CN5") (pin "3") (pinfunction "3_3") (pintype "passive"))
      (node (ref "CN6") (pin "3") (pinfunction "3_3") (pintype "passive"))
      (node (ref "CN7") (pin "3") (pinfunction "3_3") (pintype "passive"))
      (node (ref "E1") (pin "2") (pinfunction "K_2") (pintype "passive"))
      (node (ref "E2") (pin "2") (pinfunction "K_2") (pintype "passive"))
      (node (ref "E3") (pin "2") (pinfunction "K_2") (pintype "passive"))
      (node (ref "E4") (pin "2") (pinfunction "K_2") (pintype "passive"))
      (node (ref "JP1") (pin "18") (pinfunction "18_18") (pintype "passive"))
      (node (ref "JP2") (pin "4") (pinfunction "4_4") (pintype "passive"))
      (node (ref "JP3") (pin "4") (pinfunction "4_4") (pintype "passive"))
      (node (ref "JP4") (pin "4") (pinfunction "4_4") (pintype "passive"))
      (node (ref "LED1") (pin "2") (pinfunction "K_2") (pintype "passive"))
      (node (ref "P1") (pin "1") (pinfunction "1_1") (pintype "passive"))
      (node (ref "R23") (pin "2") (pinfunction "2_2") (pintype "passive"))
      (node (ref "RP1") (pin "3") (pinfunction "3_3") (pintype "passive"))
      (node (ref "S3") (pin "2") (pinfunction "2_2") (pintype "passive"))
      (node (ref "SW1") (pin "4") (pinfunction "-_4") (pintype "passive"))
      (node (ref "SW10") (pin "4") (pinfunction "-_4") (pintype "passive"))
      (node (ref "SW11") (pin "4") (pinfunction "-_4") (pintype "passive"))
      (node (ref "SW12") (pin "4") (pinfunction "-_4") (pintype "passive"))
      (node (ref "SW13") (pin "4") (pinfunction "-_4") (pintype "passive"))
      (node (ref "SW14") (pin "4") (pinfunction "-_4") (pintype "passive"))
      (node (ref "SW15") (pin "4") (pinfunction "-_4") (pintype "passive"))
      (node (ref "SW16") (pin "4") (pinfunction "-_4") (pintype "passive"))
      (node (ref "SW17") (pin "4") (pinfunction "-_4") (pintype "passive"))
      (node (ref "SW18") (pin "4") (pinfunction "-_4") (pintype "passive"))
      (node (ref "SW19") (pin "4") (pinfunction "-_4") (pintype "passive"))
      (node (ref "SW2") (pin "4") (pinfunction "-_4") (pintype "passive"))
      (node (ref "SW20") (pin "4") (pinfunction "-_4") (pintype "passive"))
      (node (ref "SW3") (pin "4") (pinfunction "-_4") (pintype "passive"))
      (node (ref "SW4") (pin "4") (pinfunction "-_4") (pintype "passive"))
      (node (ref "SW5") (pin "4") (pinfunction "-_4") (pintype "passive"))
      (node (ref "SW6") (pin "4") (pinfunction "-_4") (pintype "passive"))
      (node (ref "SW7") (pin "4") (pinfunction "-_4") (pintype "passive"))
      (node (ref "SW8") (pin "4") (pinfunction "-_4") (pintype "passive"))
      (node (ref "SW9") (pin "4") (pinfunction "-_4") (pintype "passive"))
      (node (ref "U1") (pin "23") (pinfunction "VSS_1_23") (pintype "power_in"))
      (node (ref "U1") (pin "35") (pinfunction "VSS_2_35") (pintype "power_in"))
      (node (ref "U1") (pin "47") (pinfunction "VSS_3_47") (pintype "power_in"))
      (node (ref "U1") (pin "8") (pinfunction "VSSA_8") (pintype "power_in"))
      (node (ref "USB1") (pin "4") (pinfunction "GND_4") (pintype "passive"))
      (node (ref "V1") (pin "1") (pinfunction "GND_1") (pintype "passive"))
    )
    (net (code "45") (name "Net-(LED1-A)") (class "Default")
      (node (ref "LED1") (pin "1") (pinfunction "A_1") (pintype "passive"))
      (node (ref "R27") (pin "2") (pinfunction "2_2") (pintype "passive"))
    )
    (net (code "46") (name "Net-(P2-Pad2)") (class "Default")
      (node (ref "P2") (pin "2") (pinfunction "2_2") (pintype "passive"))
      (node (ref "RP1") (pin "1") (pinfunction "1_1") (pintype "passive"))
    )
    (net (code "47") (name "Net-(SW1-+)") (class "Default")
      (node (ref "R1") (pin "1") (pinfunction "1_1") (pintype "passive"))
      (node (ref "SW1") (pin "3") (pinfunction "+_3") (pintype "passive"))
    )
    (net (code "48") (name "Net-(SW2-+)") (class "Default")
      (node (ref "R2") (pin "1") (pinfunction "1_1") (pintype "passive"))
      (node (ref "SW2") (pin "3") (pinfunction "+_3") (pintype "passive"))
    )
    (net (code "49") (name "Net-(SW3-+)") (class "Default")
      (node (ref "R3") (pin "1") (pinfunction "1_1") (pintype "passive"))
      (node (ref "SW3") (pin "3") (pinfunction "+_3") (pintype "passive"))
    )
    (net (code "50") (name "Net-(SW4-+)") (class "Default")
      (node (ref "R4") (pin "1") (pinfunction "1_1") (pintype "passive"))
      (node (ref "SW4") (pin "3") (pinfunction "+_3") (pintype "passive"))
    )
    (net (code "51") (name "Net-(SW5-+)") (class "Default")
      (node (ref "R5") (pin "1") (pinfunction "1_1") (pintype "passive"))
      (node (ref "SW5") (pin "3") (pinfunction "+_3") (pintype "passive"))
    )
    (net (code "52") (name "Net-(SW6-+)") (class "Default")
      (node (ref "R6") (pin "1") (pinfunction "1_1") (pintype "passive"))
      (node (ref "SW6") (pin "3") (pinfunction "+_3") (pintype "passive"))
    )
    (net (code "53") (name "Net-(SW7-+)") (class "Default")
      (node (ref "R7") (pin "1") (pinfunction "1_1") (pintype "passive"))
      (node (ref "SW7") (pin "3") (pinfunction "+_3") (pintype "passive"))
    )
    (net (code "54") (name "Net-(SW8-+)") (class "Default")
      (node (ref "R8") (pin "1") (pinfunction "1_1") (pintype "passive"))
      (node (ref "SW8") (pin "3") (pinfunction "+_3") (pintype "passive"))
    )
    (net (code "55") (name "Net-(SW9-+)") (class "Default")
      (node (ref "R9") (pin "1") (pinfunction "1_1") (pintype "passive"))
      (node (ref "SW9") (pin "3") (pinfunction "+_3") (pintype "passive"))
    )
    (net (code "56") (name "Net-(SW10-+)") (class "Default")
      (node (ref "R10") (pin "1") (pinfunction "1_1") (pintype "passive"))
      (node (ref "SW10") (pin "3") (pinfunction "+_3") (pintype "passive"))
    )
    (net (code "57") (name "Net-(SW11-+)") (class "Default")
      (node (ref "R11") (pin "1") (pinfunction "1_1") (pintype "passive"))
      (node (ref "SW11") (pin "3") (pinfunction "+_3") (pintype "passive"))
    )
    (net (code "58") (name "Net-(SW12-+)") (class "Default")
      (node (ref "R12") (pin "1") (pinfunction "1_1") (pintype "passive"))
      (node (ref "SW12") (pin "3") (pinfunction "+_3") (pintype "passive"))
    )
    (net (code "59") (name "Net-(SW13-+)") (class "Default")
      (node (ref "R13") (pin "1") (pinfunction "1_1") (pintype "passive"))
      (node (ref "SW13") (pin "3") (pinfunction "+_3") (pintype "passive"))
    )
    (net (code "60") (name "Net-(SW14-+)") (class "Default")
      (node (ref "R14") (pin "1") (pinfunction "1_1") (pintype "passive"))
      (node (ref "SW14") (pin "3") (pinfunction "+_3") (pintype "passive"))
    )
    (net (code "61") (name "Net-(SW15-+)") (class "Default")
      (node (ref "R15") (pin "1") (pinfunction "1_1") (pintype "passive"))
      (node (ref "SW15") (pin "3") (pinfunction "+_3") (pintype "passive"))
    )
    (net (code "62") (name "Net-(SW16-+)") (class "Default")
      (node (ref "R16") (pin "1") (pinfunction "1_1") (pintype "passive"))
      (node (ref "SW16") (pin "3") (pinfunction "+_3") (pintype "passive"))
    )
    (net (code "63") (name "Net-(SW17-+)") (class "Default")
      (node (ref "R17") (pin "1") (pinfunction "1_1") (pintype "passive"))
      (node (ref "SW17") (pin "3") (pinfunction "+_3") (pintype "passive"))
    )
    (net (code "64") (name "Net-(SW18-+)") (class "Default")
      (node (ref "R18") (pin "1") (pinfunction "1_1") (pintype "passive"))
      (node (ref "SW18") (pin "3") (pinfunction "+_3") (pintype "passive"))
    )
    (net (code "65") (name "Net-(SW19-+)") (class "Default")
      (node (ref "R19") (pin "1") (pinfunction "1_1") (pintype "passive"))
      (node (ref "SW19") (pin "3") (pinfunction "+_3") (pintype "passive"))
    )
    (net (code "66") (name "Net-(SW20-+)") (class "Default")
      (node (ref "R20") (pin "1") (pinfunction "1_1") (pintype "passive"))
      (node (ref "SW20") (pin "3") (pinfunction "+_3") (pintype "passive"))
    )
    (net (code "67") (name "Net-(U1A-PD0-OSC_IN)") (class "Default")
      (node (ref "C7") (pin "1") (pinfunction "1_1") (pintype "passive"))
      (node (ref "R21") (pin "2") (pinfunction "2_2") (pintype "passive"))
      (node (ref "U1") (pin "5") (pinfunction "PD0-OSC_IN_5") (pintype "bidirectional"))
      (node (ref "X1") (pin "2") (pinfunction "2_2") (pintype "passive"))
    )
    (net (code "68") (name "Net-(U1A-PD1)") (class "Default")
      (node (ref "C6") (pin "1") (pinfunction "1_1") (pintype "passive"))
      (node (ref "R21") (pin "1") (pinfunction "1_1") (pintype "passive"))
      (node (ref "U1") (pin "6") (pinfunction "PD1_6") (pintype "bidirectional"))
      (node (ref "X1") (pin "1") (pinfunction "1_1") (pintype "passive"))
    )
    (net (code "69") (name "VCC3.3") (class "Default")
      (node (ref "C1") (pin "2") (pinfunction "2_2") (pintype "passive"))
      (node (ref "C11") (pin "2") (pinfunction "2_2") (pintype "passive"))
      (node (ref "C2") (pin "1") (pinfunction "1_1") (pintype "passive"))
      (node (ref "C3") (pin "1") (pinfunction "1_1") (pintype "passive"))
      (node (ref "C4") (pin "2") (pinfunction "2_2") (pintype "passive"))
      (node (ref "C5") (pin "2") (pinfunction "2_2") (pintype "passive"))
      (node (ref "C8") (pin "2") (pinfunction "2_2") (pintype "passive"))
      (node (ref "CN1") (pin "1") (pinfunction "1_1") (pintype "passive"))
      (node (ref "CN2") (pin "1") (pinfunction "1_1") (pintype "passive"))
      (node (ref "CN3") (pin "1") (pinfunction "1_1") (pintype "passive"))
      (node (ref "CN4") (pin "1") (pinfunction "1_1") (pintype "passive"))
      (node (ref "CN5") (pin "1") (pinfunction "1_1") (pintype "passive"))
      (node (ref "E3") (pin "1") (pinfunction "A_1") (pintype "passive"))
      (node (ref "E4") (pin "1") (pinfunction "A_1") (pintype "passive"))
      (node (ref "P1") (pin "4") (pinfunction "4_4") (pintype "passive"))
      (node (ref "R22") (pin "2") (pinfunction "2_2") (pintype "passive"))
      (node (ref "R26") (pin "1") (pinfunction "1_1") (pintype "passive"))
      (node (ref "U1") (pin "1") (pinfunction "VBAT_1") (pintype "power_in"))
      (node (ref "U1") (pin "24") (pinfunction "VDD_1_24") (pintype "power_in"))
      (node (ref "U1") (pin "36") (pinfunction "VDD_2_36") (pintype "power_in"))
      (node (ref "U1") (pin "48") (pinfunction "VDD_3_48") (pintype "power_in"))
      (node (ref "U1") (pin "9") (pinfunction "VDDA_9") (pintype "power_in"))
      (node (ref "V1") (pin "2") (pinfunction "Vout_2") (pintype "passive"))
    )
  )
)
